# lcd_duffle_smd_mk_2.net
KiCad netlist of a schematic drawn in EAGLE
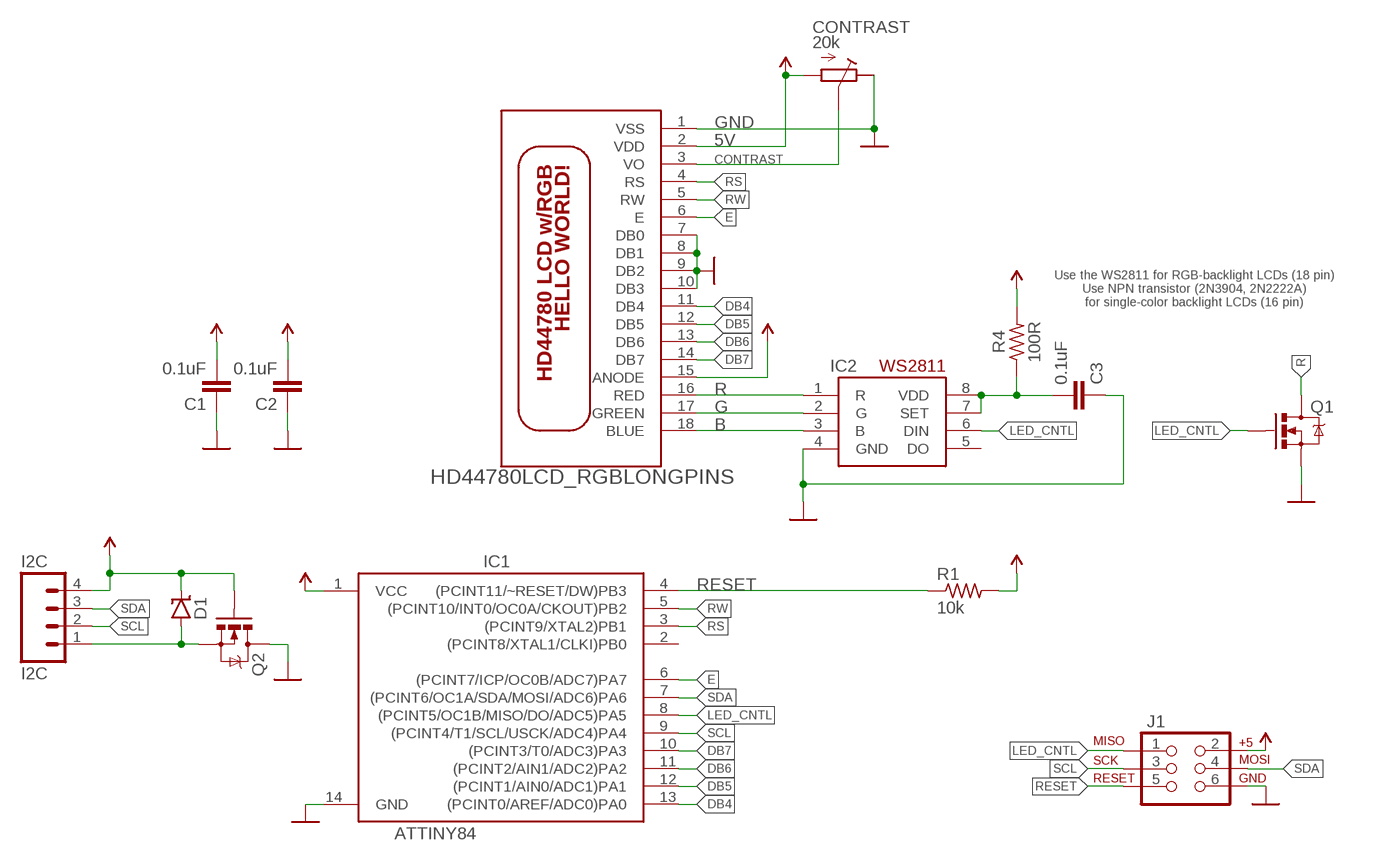
[diagram p0: schematic, sheet 1]

(export (version "E")
  (design (tool "Eeschema 10.0.6"))
  (components
    (comp (ref "C1")
      (value "0.1uF")
      (footprint "eagle-import:C0603")
      (libsource (lib "eagle-import") (part "CAPACITOR-CERAMICC0603"))
    )
    (comp (ref "C2")
      (value "0.1uF")
      (footprint "eagle-import:C0603")
      (libsource (lib "eagle-import") (part "CAPACITOR-CERAMICC0603"))
    )
    (comp (ref "C3")
      (value "0.1uF")
      (footprint "eagle-import:C0603")
      (libsource (lib "eagle-import") (part "CAPACITOR-CERAMICC0603"))
    )
    (comp (ref "CONTRAST")
      (value "20k")
      (footprint "eagle-import:POT-THUMBWHEEL")
      (libsource (lib "eagle-import") (part "POTENTIOMETERTHUMBWHEEL-16MM"))
    )
    (comp (ref "D1")
      (value "DIODE-ZENERSOD123")
      (footprint "eagle-import:SOD123")
      (libsource (lib "eagle-import") (part "DIODE-ZENERSOD123"))
    )
    (comp (ref "I2C")
      (value "I2C")
      (footprint "eagle-import:1X04-SMD")
      (libsource (lib "eagle-import") (part "M04SMD"))
    )
    (comp (ref "IC1")
      (value "ATTINY84")
      (footprint "eagle-import:SO14")
      (libsource (lib "eagle-import") (part "ATTINY84"))
    )
    (comp (ref "IC2")
      (value "WS2811")
      (footprint "eagle-import:SO08-SKINNYPADS")
      (libsource (lib "eagle-import") (part "WS2811-SOP8"))
    )
    (comp (ref "J1")
      (value "AVR_SPI_PRG_6TESTPOINTS")
      (footprint "eagle-import:2X3_TEST_POINTS")
      (libsource (lib "eagle-import") (part "AVR_SPI_PRG_6TESTPOINTS"))
    )
    (comp (ref "Q1")
      (value "MOSFET-NCHANNELIRLML2502")
      (footprint "eagle-import:SOT23")
      (libsource (lib "eagle-import") (part "MOSFET-NCHANNELIRLML2502"))
    )
    (comp (ref "Q2")
      (value "MOSFET-NCHANNELIRLML2502")
      (footprint "eagle-import:SOT23")
      (libsource (lib "eagle-import") (part "MOSFET-NCHANNELIRLML2502"))
    )
    (comp (ref "R1")
      (value "10k")
      (footprint "eagle-import:R0603")
      (libsource (lib "eagle-import") (part "RESISTORR0603"))
    )
    (comp (ref "R4")
      (value "100R")
      (footprint "eagle-import:R0603")
      (libsource (lib "eagle-import") (part "RESISTORR0603"))
    )
    (comp (ref "U$1")
      (value "HD44780LCD_RGBLONGPINS")
      (footprint "eagle-import:LCD1602-RGB-CENTERED")
      (libsource (lib "eagle-import") (part "HD44780LCD_RGBLONGPINS"))
    )
  )
  (nets
    (net (code "1") (name "/B") (class "Default")
      (node (ref "IC2") (pin "3") (pinfunction "B_3") (pintype "open_collector"))
      (node (ref "U$1") (pin "18") (pinfunction "BLUE_18") (pintype "input"))
    )
    (net (code "2") (name "/CONTRAST") (class "Default")
      (node (ref "CONTRAST") (pin "2") (pinfunction "S_2") (pintype "passive"))
      (node (ref "CONTRAST") (pin "2@1") (pinfunction "S_2@1") (pintype "passive"))
      (node (ref "U$1") (pin "3") (pinfunction "VO_3") (pintype "input"))
    )
    (net (code "3") (name "/G") (class "Default")
      (node (ref "IC2") (pin "2") (pinfunction "G_2") (pintype "open_collector"))
      (node (ref "U$1") (pin "17") (pinfunction "GREEN_17") (pintype "input"))
    )
    (net (code "4") (name "5V") (class "Default")
      (node (ref "C1") (pin "2") (pinfunction "2_2") (pintype "passive"))
      (node (ref "C2") (pin "2") (pinfunction "2_2") (pintype "passive"))
      (node (ref "CONTRAST") (pin "1") (pinfunction "A_1") (pintype "passive"))
      (node (ref "D1") (pin "C") (pinfunction "C_C") (pintype "passive"))
      (node (ref "I2C") (pin "4") (pinfunction "4_4") (pintype "passive"))
      (node (ref "IC1") (pin "1") (pinfunction "VCC_1") (pintype "bidirectional"))
      (node (ref "J1") (pin "2") (pinfunction "2_2") (pintype "passive"))
      (node (ref "Q2") (pin "1") (pinfunction "G_1") (pintype "passive"))
      (node (ref "R1") (pin "2") (pinfunction "2_2") (pintype "passive"))
      (node (ref "R4") (pin "2") (pinfunction "2_2") (pintype "passive"))
      (node (ref "U$1") (pin "15") (pinfunction "ANODE_15") (pintype "input"))
      (node (ref "U$1") (pin "2") (pinfunction "VDD_2") (pintype "power_in"))
    )
    (net (code "5") (name "DB4") (class "Default")
      (node (ref "IC1") (pin "13") (pinfunction "(PCINT0/AREF/ADC0)PA0_13") (pintype "bidirectional"))
      (node (ref "U$1") (pin "11") (pinfunction "DB4_11") (pintype "bidirectional"))
    )
    (net (code "6") (name "DB5") (class "Default")
      (node (ref "IC1") (pin "12") (pinfunction "(PCINT1/AIN0/ADC1)PA1_12") (pintype "bidirectional"))
      (node (ref "U$1") (pin "12") (pinfunction "DB5_12") (pintype "bidirectional"))
    )
    (net (code "7") (name "DB6") (class "Default")
      (node (ref "IC1") (pin "11") (pinfunction "(PCINT2/AIN1/ADC2)PA2_11") (pintype "bidirectional"))
      (node (ref "U$1") (pin "13") (pinfunction "DB6_13") (pintype "bidirectional"))
    )
    (net (code "8") (name "DB7") (class "Default")
      (node (ref "IC1") (pin "10") (pinfunction "(PCINT3/T0/ADC3)PA3_10") (pintype "bidirectional"))
      (node (ref "U$1") (pin "14") (pinfunction "DB7_14") (pintype "bidirectional"))
    )
    (net (code "9") (name "E") (class "Default")
      (node (ref "IC1") (pin "6") (pinfunction "(PCINT7/ICP/OC0B/ADC7)PA7_6") (pintype "bidirectional"))
      (node (ref "U$1") (pin "6") (pinfunction "E_6") (pintype "input"))
    )
    (net (code "10") (name "GND") (class "Default")
      (node (ref "C1") (pin "1") (pinfunction "1_1") (pintype "passive"))
      (node (ref "C2") (pin "1") (pinfunction "1_1") (pintype "passive"))
      (node (ref "C3") (pin "1") (pinfunction "1_1") (pintype "passive"))
      (node (ref "CONTRAST") (pin "3") (pinfunction "E_3") (pintype "passive"))
      (node (ref "IC1") (pin "14") (pinfunction "GND_14") (pintype "bidirectional"))
      (node (ref "IC2") (pin "4") (pinfunction "GND_4") (pintype "power_in"))
      (node (ref "J1") (pin "6") (pinfunction "6_6") (pintype "passive"))
      (node (ref "Q1") (pin "2") (pinfunction "S_2") (pintype "passive"))
      (node (ref "Q2") (pin "3") (pinfunction "D_3") (pintype "passive"))
      (node (ref "U$1") (pin "1") (pinfunction "VSS_1") (pintype "power_in"))
      (node (ref "U$1") (pin "10") (pinfunction "DB3_10") (pintype "bidirectional"))
      (node (ref "U$1") (pin "7") (pinfunction "DB0_7") (pintype "bidirectional"))
      (node (ref "U$1") (pin "8") (pinfunction "DB1_8") (pintype "bidirectional"))
      (node (ref "U$1") (pin "9") (pinfunction "DB2_9") (pintype "bidirectional"))
    )
    (net (code "11") (name "LED_CNTL") (class "Default")
      (node (ref "IC1") (pin "8") (pinfunction "(PCINT5/OC1B/MISO/DO/ADC5)PA5_8") (pintype "bidirectional"))
      (node (ref "IC2") (pin "6") (pinfunction "DIN_6") (pintype "input"))
      (node (ref "J1") (pin "1") (pinfunction "1_1") (pintype "passive"))
      (node (ref "Q1") (pin "1") (pinfunction "G_1") (pintype "passive"))
    )
    (net (code "12") (name "Net-(IC2-SET)") (class "Default")
      (node (ref "C3") (pin "2") (pinfunction "2_2") (pintype "passive"))
      (node (ref "IC2") (pin "7") (pinfunction "SET_7") (pintype "input"))
      (node (ref "IC2") (pin "8") (pinfunction "VDD_8") (pintype "power_in"))
      (node (ref "R4") (pin "1") (pinfunction "1_1") (pintype "passive"))
    )
    (net (code "13") (name "Net-(Q2-S)") (class "Default")
      (node (ref "D1") (pin "A") (pinfunction "A_A") (pintype "passive"))
      (node (ref "I2C") (pin "1") (pinfunction "1_1") (pintype "passive"))
      (node (ref "Q2") (pin "2") (pinfunction "S_2") (pintype "passive"))
    )
    (net (code "14") (name "R") (class "Default")
      (node (ref "IC2") (pin "1") (pinfunction "R_1") (pintype "open_collector"))
      (node (ref "Q1") (pin "3") (pinfunction "D_3") (pintype "passive"))
      (node (ref "U$1") (pin "16") (pinfunction "RED_16") (pintype "input"))
    )
    (net (code "15") (name "RESET") (class "Default")
      (node (ref "IC1") (pin "4") (pinfunction "(PCINT11/~{RESET/DW})PB3_4") (pintype "bidirectional"))
      (node (ref "J1") (pin "5") (pinfunction "5_5") (pintype "passive"))
      (node (ref "R1") (pin "1") (pinfunction "1_1") (pintype "passive"))
    )
    (net (code "16") (name "RS") (class "Default")
      (node (ref "IC1") (pin "3") (pinfunction "(PCINT9/XTAL2)PB1_3") (pintype "bidirectional"))
      (node (ref "U$1") (pin "4") (pinfunction "RS_4") (pintype "input"))
    )
    (net (code "17") (name "RW") (class "Default")
      (node (ref "IC1") (pin "5") (pinfunction "(PCINT10/INT0/OC0A/CKOUT)PB2_5") (pintype "bidirectional"))
      (node (ref "U$1") (pin "5") (pinfunction "RW_5") (pintype "input"))
    )
    (net (code "18") (name "SCL") (class "Default")
      (node (ref "I2C") (pin "2") (pinfunction "2_2") (pintype "passive"))
      (node (ref "IC1") (pin "9") (pinfunction "(PCINT4/T1/SCL/USCK/ADC4)PA4_9") (pintype "bidirectional"))
      (node (ref "J1") (pin "3") (pinfunction "3_3") (pintype "passive"))
    )
    (net (code "19") (name "SDA") (class "Default")
      (node (ref "I2C") (pin "3") (pinfunction "3_3") (pintype "passive"))
      (node (ref "IC1") (pin "7") (pinfunction "(PCINT6/OC1A/SDA/MOSI/ADC6)PA6_7") (pintype "bidirectional"))
      (node (ref "J1") (pin "4") (pinfunction "4_4") (pintype "passive"))
    )
    (net (code "20") (name "unconnected-(IC1-(PCINT8{slash}XTAL1{slash}CLKI)PB0-Pad2)") (class "Default")
      (node (ref "IC1") (pin "2") (pinfunction "(PCINT8/XTAL1/CLKI)PB0_2") (pintype "bidirectional"))
    )
    (net (code "21") (name "unconnected-(IC2-DO-Pad5)") (class "Default")
      (node (ref "IC2") (pin "5") (pinfunction "DO_5") (pintype "output"))
    )
  )
)
